# DRIVER.net
KiCad netlist of a schematic drawn in Altium Designer
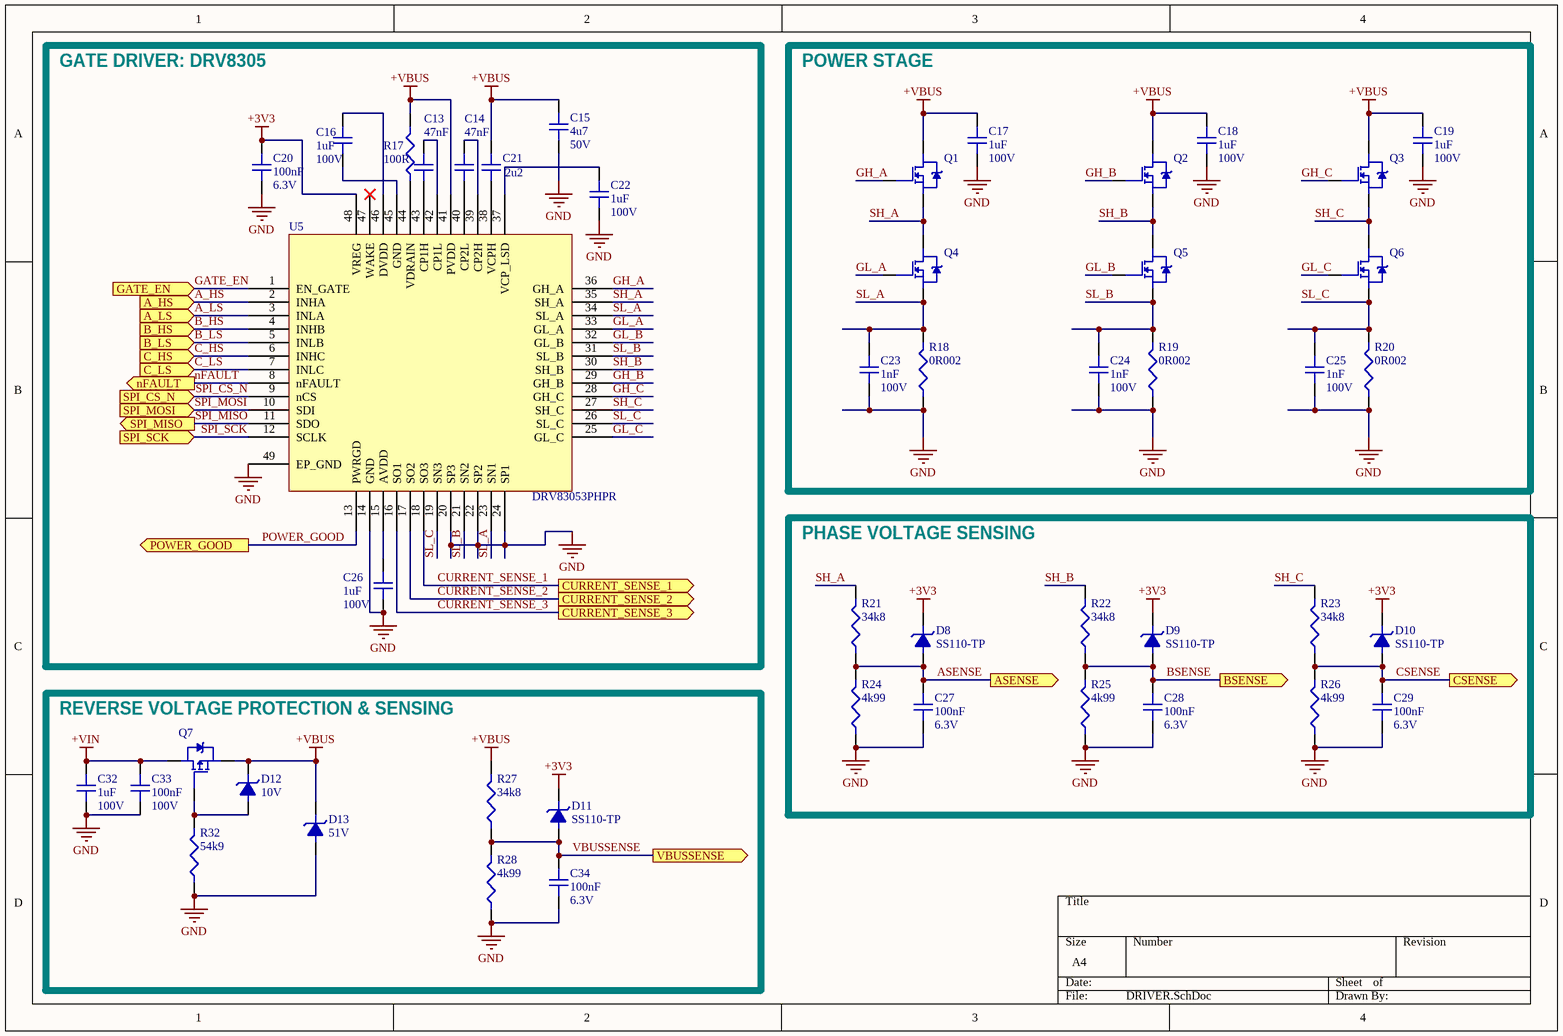
[diagram p0: DRIVER.SchDoc]

(export (version "E")
  (design (tool "Eeschema 10.0.6"))
  (components
    (comp (ref "C13")
      (value "47nF")
      (footprint "C0402")
      (description "CAP CER 0.047uF 50 V,  10%, X7R, CGA Series")
      (fields
        (field (name "MANUFACTURER") "TDK")
        (field (name "MANUFACTURER PART NUMBER") "CGA2B3X7R1H473K050BB")
      )
      (libsource (lib "ESC_SYMBOLS") (part "CGA2B3X7R1H473K050BB"))
    )
    (comp (ref "C14")
      (value "47nF")
      (footprint "C0402")
      (description "CAP CER 0.047uF 50 V,  10%, X7R, CGA Series")
      (fields
        (field (name "MANUFACTURER") "TDK")
        (field (name "MANUFACTURER PART NUMBER") "CGA2B3X7R1H473K050BB")
      )
      (libsource (lib "ESC_SYMBOLS") (part "CGA2B3X7R1H473K050BB"))
    )
    (comp (ref "C15")
      (value "4u7")
      (footprint "C0805")
      (description "CAP CER 4.7uF 50V X5R 10% SMD 0805 85C Embossed T/R")
      (fields
        (field (name "MANUFACTURER") "Samsung")
        (field (name "MANUFACTURER PART NUMBER") "CL21A475KBQNNNE")
        (field (name "VOLTAGE RATING") "50V")
      )
      (libsource (lib "ESC_SYMBOLS") (part "CL21A475KBQNNNE"))
    )
    (comp (ref "C16")
      (value "1uF")
      (footprint "C0805")
      (description "CAP CER 1UF 100V X7S 0805")
      (fields
        (field (name "MANUFACTURER") "TDK")
        (field (name "MANUFACTURER PART NUMBER") "C2012X7S2A105M125AE")
        (field (name "VOLTAGE RATING") "100V")
      )
      (libsource (lib "ESC_SYMBOLS") (part "C2012X7S2A105M125AE"))
    )
    (comp (ref "C17")
      (value "1uF")
      (footprint "C0805")
      (description "CAP CER 1UF 100V X7S 0805")
      (fields
        (field (name "MANUFACTURER") "TDK")
        (field (name "MANUFACTURER PART NUMBER") "C2012X7S2A105M125AE")
        (field (name "VOLTAGE RATING") "100V")
      )
      (libsource (lib "ESC_SYMBOLS") (part "C2012X7S2A105M125AE"))
    )
    (comp (ref "C18")
      (value "1uF")
      (footprint "C0805")
      (description "CAP CER 1UF 100V X7S 0805")
      (fields
        (field (name "MANUFACTURER") "TDK")
        (field (name "MANUFACTURER PART NUMBER") "C2012X7S2A105M125AE")
        (field (name "VOLTAGE RATING") "100V")
      )
      (libsource (lib "ESC_SYMBOLS") (part "C2012X7S2A105M125AE"))
    )
    (comp (ref "C19")
      (value "1uF")
      (footprint "C0805")
      (description "CAP CER 1UF 100V X7S 0805")
      (fields
        (field (name "MANUFACTURER") "TDK")
        (field (name "MANUFACTURER PART NUMBER") "C2012X7S2A105M125AE")
        (field (name "VOLTAGE RATING") "100V")
      )
      (libsource (lib "ESC_SYMBOLS") (part "C2012X7S2A105M125AE"))
    )
    (comp (ref "C20")
      (value "100nF")
      (footprint "C0402")
      (description "CAP CER 0.1uF 6.3V X7R 10% SMD 0402 125C Paper T/R")
      (fields
        (field (name "MANUFACTURER") "Samsung")
        (field (name "MANUFACTURER PART NUMBER") "CL05B104KQ5NNNC")
        (field (name "VOLTAGE RATING") "6.3V")
      )
      (libsource (lib "ESC_SYMBOLS") (part "CL05B104KQ5NNNC"))
    )
    (comp (ref "C21")
      (value "2u2")
      (footprint "C0805")
      (description "CAP CER 2.2UF 50V X5R 0805")
      (fields
        (field (name "MANUFACTURER") "TDK")
        (field (name "MANUFACTURER PART NUMBER") "C2012X5R1H225M125AB")
      )
      (libsource (lib "ESC_SYMBOLS") (part "C2012X5R1H225M125AB"))
    )
    (comp (ref "C22")
      (value "1uF")
      (footprint "C0805")
      (description "CAP CER 1UF 100V X7S 0805")
      (fields
        (field (name "MANUFACTURER") "TDK")
        (field (name "MANUFACTURER PART NUMBER") "C2012X7S2A105M125AE")
        (field (name "VOLTAGE RATING") "100V")
      )
      (libsource (lib "ESC_SYMBOLS") (part "C2012X7S2A105M125AE"))
    )
    (comp (ref "C23")
      (value "1nF")
      (footprint "C0402")
      (description "CAP CER 1000PF 100V X7R 0402")
      (fields
        (field (name "MANUFACTURER") "Murata")
        (field (name "MANUFACTURER PART NUMBER") "GCM155R72A102KA37D")
        (field (name "VOLTAGE") "100V")
      )
      (libsource (lib "ESC_SYMBOLS") (part "GCM155R72A102KA37D"))
    )
    (comp (ref "C24")
      (value "1nF")
      (footprint "C0402")
      (description "CAP CER 1000PF 100V X7R 0402")
      (fields
        (field (name "MANUFACTURER") "Murata")
        (field (name "MANUFACTURER PART NUMBER") "GCM155R72A102KA37D")
        (field (name "VOLTAGE") "100V")
      )
      (libsource (lib "ESC_SYMBOLS") (part "GCM155R72A102KA37D"))
    )
    (comp (ref "C25")
      (value "1nF")
      (footprint "C0402")
      (description "CAP CER 1000PF 100V X7R 0402")
      (fields
        (field (name "MANUFACTURER") "Murata")
        (field (name "MANUFACTURER PART NUMBER") "GCM155R72A102KA37D")
        (field (name "VOLTAGE") "100V")
      )
      (libsource (lib "ESC_SYMBOLS") (part "GCM155R72A102KA37D"))
    )
    (comp (ref "C26")
      (value "1uF")
      (footprint "C0805")
      (description "CAP CER 1UF 100V X7S 0805")
      (fields
        (field (name "MANUFACTURER") "TDK")
        (field (name "MANUFACTURER PART NUMBER") "C2012X7S2A105M125AE")
        (field (name "VOLTAGE RATING") "100V")
      )
      (libsource (lib "ESC_SYMBOLS") (part "C2012X7S2A105M125AE"))
    )
    (comp (ref "C27")
      (value "100nF")
      (footprint "C0402")
      (description "CAP CER 0.1uF 6.3V X7R 10% SMD 0402 125C Paper T/R")
      (fields
        (field (name "MANUFACTURER") "Samsung")
        (field (name "MANUFACTURER PART NUMBER") "CL05B104KQ5NNNC")
        (field (name "VOLTAGE RATING") "6.3V")
      )
      (libsource (lib "ESC_SYMBOLS") (part "CL05B104KQ5NNNC"))
    )
    (comp (ref "C28")
      (value "100nF")
      (footprint "C0402")
      (description "CAP CER 0.1uF 6.3V X7R 10% SMD 0402 125C Paper T/R")
      (fields
        (field (name "MANUFACTURER") "Samsung")
        (field (name "MANUFACTURER PART NUMBER") "CL05B104KQ5NNNC")
        (field (name "VOLTAGE RATING") "6.3V")
      )
      (libsource (lib "ESC_SYMBOLS") (part "CL05B104KQ5NNNC"))
    )
    (comp (ref "C29")
      (value "100nF")
      (footprint "C0402")
      (description "CAP CER 0.1uF 6.3V X7R 10% SMD 0402 125C Paper T/R")
      (fields
        (field (name "MANUFACTURER") "Samsung")
        (field (name "MANUFACTURER PART NUMBER") "CL05B104KQ5NNNC")
        (field (name "VOLTAGE RATING") "6.3V")
      )
      (libsource (lib "ESC_SYMBOLS") (part "CL05B104KQ5NNNC"))
    )
    (comp (ref "C32")
      (value "1uF")
      (footprint "C0805")
      (description "CAP CER 1UF 100V X7S 0805")
      (fields
        (field (name "MANUFACTURER") "TDK")
        (field (name "MANUFACTURER PART NUMBER") "C2012X7S2A105M125AE")
        (field (name "VOLTAGE RATING") "100V")
      )
      (libsource (lib "ESC_SYMBOLS") (part "C2012X7S2A105M125AE"))
    )
    (comp (ref "C33")
      (value "100nF")
      (footprint "C0805")
      (fields
        (field (name "MANUFACTURER") "Samsung")
        (field (name "MANUFACTURER PART NUMBER") "CL21B104KCFWPNE")
        (field (name "TOLERANCE") "10%")
        (field (name "VOLTAGE RATING") "100V")
      )
      (libsource (lib "ESC_SYMBOLS") (part "CL21B104KCFWPNE"))
    )
    (comp (ref "C34")
      (value "100nF")
      (footprint "C0805")
      (description "CAP CER 0.10uF 6.3V X7R MLCC - SMD/SMT 6.3volts 0.1uF X7R 10%")
      (fields
        (field (name "MANUFACTURER") "KEMET")
        (field (name "MANUFACTURER PART NUMBER") "C0805C104K9RACTU")
        (field (name "VOLTAGE RATING") "6.3V")
      )
      (libsource (lib "ESC_SYMBOLS") (part "C0805C104K9RACTU"))
    )
    (comp (ref "D8")
      (value "SS110-TP")
      (footprint "DO-214AA_Diode")
      (description "DIODE SCHOTTKY 100V 1A SMA")
      (fields (field (name "MANUFACTURER") "MCC"))
      (libsource (lib "ESC_SYMBOLS") (part "SS110-TP"))
    )
    (comp (ref "D9")
      (value "SS110-TP")
      (footprint "DO-214AA_Diode")
      (description "DIODE SCHOTTKY 100V 1A SMA")
      (fields (field (name "MANUFACTURER") "MCC"))
      (libsource (lib "ESC_SYMBOLS") (part "SS110-TP"))
    )
    (comp (ref "D10")
      (value "SS110-TP")
      (footprint "DO-214AA_Diode")
      (description "DIODE SCHOTTKY 100V 1A SMA")
      (fields (field (name "MANUFACTURER") "MCC"))
      (libsource (lib "ESC_SYMBOLS") (part "SS110-TP"))
    )
    (comp (ref "D11")
      (value "SS110-TP")
      (footprint "DO-214AA_Diode")
      (description "DIODE SCHOTTKY 100V 1A SMA")
      (fields (field (name "MANUFACTURER") "MCC"))
      (libsource (lib "ESC_SYMBOLS") (part "SS110-TP"))
    )
    (comp (ref "D12")
      (value "10V")
      (footprint "DO-214AC")
      (description "DIODE ZENER 10V 5% 1W 2-Pin SMA T/R")
      (fields (field (name "MANUFACTURER") "Diodes") (field (name "MANUFACTURER PART NUMBER") "SMAZ10-13-F"))
      (libsource (lib "ESC_SYMBOLS") (part "SMAZ10-13-F"))
    )
    (comp (ref "D13")
      (value "51V")
      (footprint "DO-214AB")
      (description "DIODE ZENER 51V 5W")
      (fields
        (field (name "MANUFACTURER") "Taiwan Semiconductor")
        (field (name "MANUFACTURER PART NUMBER") "1PGSMC5369HR7G")
      )
      (libsource (lib "ESC_SYMBOLS") (part "1PGSMC5369HR7G"))
    )
    (comp (ref "Q1")
      (value "SIR186DP-T1-RE3")
      (footprint "SO-8 PowerPAK")
      (description "MOSFET N-CH 60V 60A 4.5mOhm Rds(ON)")
      (fields (field (name "MANUFACTURER") "Vishay Siliconix"))
      (libsource (lib "ESC_SYMBOLS") (part "SIR186DP-T1-RE3"))
    )
    (comp (ref "Q2")
      (value "SIR186DP-T1-RE3")
      (footprint "SO-8 PowerPAK")
      (description "MOSFET N-CH 60V 60A 4.5mOhm Rds(ON)")
      (fields (field (name "MANUFACTURER") "Vishay Siliconix"))
      (libsource (lib "ESC_SYMBOLS") (part "SIR186DP-T1-RE3"))
    )
    (comp (ref "Q3")
      (value "SIR186DP-T1-RE3")
      (footprint "SO-8 PowerPAK")
      (description "MOSFET N-CH 60V 60A 4.5mOhm Rds(ON)")
      (fields (field (name "MANUFACTURER") "Vishay Siliconix"))
      (libsource (lib "ESC_SYMBOLS") (part "SIR186DP-T1-RE3"))
    )
    (comp (ref "Q4")
      (value "SIR186DP-T1-RE3")
      (footprint "SO-8 PowerPAK")
      (description "MOSFET N-CH 60V 60A 4.5mOhm Rds(ON)")
      (fields (field (name "MANUFACTURER") "Vishay Siliconix"))
      (libsource (lib "ESC_SYMBOLS") (part "SIR186DP-T1-RE3"))
    )
    (comp (ref "Q5")
      (value "SIR186DP-T1-RE3")
      (footprint "SO-8 PowerPAK")
      (description "MOSFET N-CH 60V 60A 4.5mOhm Rds(ON)")
      (fields (field (name "MANUFACTURER") "Vishay Siliconix"))
      (libsource (lib "ESC_SYMBOLS") (part "SIR186DP-T1-RE3"))
    )
    (comp (ref "Q6")
      (value "SIR186DP-T1-RE3")
      (footprint "SO-8 PowerPAK")
      (description "MOSFET N-CH 60V 60A 4.5mOhm Rds(ON)")
      (fields (field (name "MANUFACTURER") "Vishay Siliconix"))
      (libsource (lib "ESC_SYMBOLS") (part "SIR186DP-T1-RE3"))
    )
    (comp (ref "Q7")
      (value "FDWS9509L-F085")
      (footprint "SO-8 PowerPAK")
      (description "MOSFET P-CH PWR56 40V 8 MOHM")
      (fields (field (name "MANUFACTURER") "ON Semiconductor"))
      (libsource (lib "ESC_SYMBOLS") (part "FDWS9509L-F085"))
    )
    (comp (ref "R17")
      (value "100R")
      (footprint "R0402")
      (description "RES SMD 100 OHM 5% 1/16W 0402")
      (fields
        (field (name "MANUFACTURER") "Yageo")
        (field (name "MANUFACTURER PART NUMBER") "RC0402JR-07100RL")
      )
      (libsource (lib "ESC_SYMBOLS") (part "RC0402JR-07100RL"))
    )
    (comp (ref "R18")
      (value "0R002")
      (footprint "R2512")
      (description "RES SMD 0.002 OHM 1% 5W 2512")
      (fields
        (field (name "MANUFACTURER") "Vishay Dale")
        (field (name "MANUFACTURER PART NUMBER") "WSLF25122L000FEA")
      )
      (libsource (lib "ESC_SYMBOLS") (part "WSLF25122L000FEA"))
    )
    (comp (ref "R19")
      (value "0R002")
      (footprint "R2512")
      (description "RES SMD 0.002 OHM 1% 5W 2512")
      (fields
        (field (name "MANUFACTURER") "Vishay Dale")
        (field (name "MANUFACTURER PART NUMBER") "WSLF25122L000FEA")
      )
      (libsource (lib "ESC_SYMBOLS") (part "WSLF25122L000FEA"))
    )
    (comp (ref "R20")
      (value "0R002")
      (footprint "R2512")
      (description "RES SMD 0.002 OHM 1% 5W 2512")
      (fields
        (field (name "MANUFACTURER") "Vishay Dale")
        (field (name "MANUFACTURER PART NUMBER") "WSLF25122L000FEA")
      )
      (libsource (lib "ESC_SYMBOLS") (part "WSLF25122L000FEA"))
    )
    (comp (ref "R21")
      (value "34k8")
      (footprint "R0402")
      (description "RES SMD 34.8K OHM 1% 1/16W 0402")
      (fields
        (field (name "MANUFACTURER") "Yageo")
        (field (name "MANUFACTURER PART NUMBER") "RC0402FR-0734K8L")
      )
      (libsource (lib "ESC_SYMBOLS") (part "RC0402FR-0734K8L"))
    )
    (comp (ref "R22")
      (value "34k8")
      (footprint "R0402")
      (description "RES SMD 34.8K OHM 1% 1/16W 0402")
      (fields
        (field (name "MANUFACTURER") "Yageo")
        (field (name "MANUFACTURER PART NUMBER") "RC0402FR-0734K8L")
      )
      (libsource (lib "ESC_SYMBOLS") (part "RC0402FR-0734K8L"))
    )
    (comp (ref "R23")
      (value "34k8")
      (footprint "R0402")
      (description "RES SMD 34.8K OHM 1% 1/16W 0402")
      (fields
        (field (name "MANUFACTURER") "Yageo")
        (field (name "MANUFACTURER PART NUMBER") "RC0402FR-0734K8L")
      )
      (libsource (lib "ESC_SYMBOLS") (part "RC0402FR-0734K8L"))
    )
    (comp (ref "R24")
      (value "4k99")
      (footprint "R0402")
      (description "RES SMD 4.99K OHM 1/16W 0402")
      (fields
        (field (name "MANUFACTURER") "Vishay")
        (field (name "MANUFACTURER PART NUMBER") "CRCW04024R99FKEDC")
      )
      (libsource (lib "ESC_SYMBOLS") (part "CRCW04024R99FKEDC"))
    )
    (comp (ref "R25")
      (value "4k99")
      (footprint "R0402")
      (description "RES SMD 4.99K OHM 1/16W 0402")
      (fields
        (field (name "MANUFACTURER") "Vishay")
        (field (name "MANUFACTURER PART NUMBER") "CRCW04024R99FKEDC")
      )
      (libsource (lib "ESC_SYMBOLS") (part "CRCW04024R99FKEDC"))
    )
    (comp (ref "R26")
      (value "4k99")
      (footprint "R0402")
      (description "RES SMD 4.99K OHM 1/16W 0402")
      (fields
        (field (name "MANUFACTURER") "Vishay")
        (field (name "MANUFACTURER PART NUMBER") "CRCW04024R99FKEDC")
      )
      (libsource (lib "ESC_SYMBOLS") (part "CRCW04024R99FKEDC"))
    )
    (comp (ref "R27")
      (value "34k8")
      (footprint "R0402")
      (description "RES SMD 34.8K OHM 1% 1/16W 0402")
      (fields
        (field (name "MANUFACTURER") "Yageo")
        (field (name "MANUFACTURER PART NUMBER") "RC0402FR-0734K8L")
      )
      (libsource (lib "ESC_SYMBOLS") (part "RC0402FR-0734K8L"))
    )
    (comp (ref "R28")
      (value "4k99")
      (footprint "R0402")
      (description "RES SMD 4.99K OHM 1/16W 0402")
      (fields
        (field (name "MANUFACTURER") "Vishay")
        (field (name "MANUFACTURER PART NUMBER") "CRCW04024R99FKEDC")
      )
      (libsource (lib "ESC_SYMBOLS") (part "CRCW04024R99FKEDC"))
    )
    (comp (ref "R32")
      (value "54k9")
      (footprint "R0402")
      (description "RES SMD 54.9K OHM 1/10W 0402 54.9 Ohm 1% 0.1W(1/10W) ±100ppm/C Molded SMD Automotive Punched T/R")
      (fields
        (field (name "MANUFACTURER") "Panasonic")
        (field (name "MANUFACTURER PART NUMBER") "ERJ-2RKF54R9X")
      )
      (libsource (lib "ESC_SYMBOLS") (part "ERJ-2RKF54R9X"))
    )
    (comp (ref "U5")
      (value "DRV83053PHPR")
      (footprint "PQFP_EP-48")
      (description "IC 3-Phase Gate Driver IC 4.4V to 45V 48-Pin HTQFP T/R")
      (fields (field (name "MANUFACTURER") "Texas Instruments"))
      (libsource (lib "ESC_SYMBOLS") (part "DRV83053PHPR"))
    )
  )
  (nets
    (net (code "1") (name "+3V3") (class "Default")
      (node (ref "C20") (pin "2") (pinfunction "2_2") (pintype "passive"))
      (node (ref "D10") (pin "2") (pinfunction "2_2") (pintype "passive"))
      (node (ref "D11") (pin "2") (pinfunction "2_2") (pintype "passive"))
      (node (ref "D8") (pin "2") (pinfunction "2_2") (pintype "passive"))
      (node (ref "D9") (pin "2") (pinfunction "2_2") (pintype "passive"))
      (node (ref "U5") (pin "48") (pinfunction "VREG_48") (pintype "passive"))
    )
    (net (code "2") (name "+VBUS") (class "Default")
      (node (ref "C15") (pin "2") (pinfunction "2_2") (pintype "passive"))
      (node (ref "C17") (pin "2") (pinfunction "2_2") (pintype "passive"))
      (node (ref "C18") (pin "2") (pinfunction "2_2") (pintype "passive"))
      (node (ref "C19") (pin "2") (pinfunction "2_2") (pintype "passive"))
      (node (ref "C21") (pin "2") (pinfunction "2_2") (pintype "passive"))
      (node (ref "D12") (pin "1") (pinfunction "1_1") (pintype "passive"))
      (node (ref "D13") (pin "1") (pinfunction "1_1") (pintype "passive"))
      (node (ref "Q1") (pin "2") (pinfunction "2_2") (pintype "passive"))
      (node (ref "Q2") (pin "2") (pinfunction "2_2") (pintype "passive"))
      (node (ref "Q3") (pin "2") (pinfunction "2_2") (pintype "passive"))
      (node (ref "Q7") (pin "3") (pinfunction "3_3") (pintype "passive"))
      (node (ref "R17") (pin "2") (pinfunction "2_2") (pintype "passive"))
      (node (ref "R27") (pin "2") (pinfunction "2_2") (pintype "passive"))
      (node (ref "U5") (pin "41") (pinfunction "PVDD_41") (pintype "passive"))
    )
    (net (code "3") (name "+VIN") (class "Default")
      (node (ref "C32") (pin "2") (pinfunction "2_2") (pintype "passive"))
      (node (ref "C33") (pin "2") (pinfunction "2_2") (pintype "passive"))
      (node (ref "Q7") (pin "2") (pinfunction "2_2") (pintype "passive"))
    )
    (net (code "4") (name "/ASENSE") (class "Default")
      (node (ref "C27") (pin "2") (pinfunction "2_2") (pintype "passive"))
      (node (ref "D8") (pin "1") (pinfunction "1_1") (pintype "passive"))
      (node (ref "R21") (pin "1") (pinfunction "1_1") (pintype "passive"))
      (node (ref "R24") (pin "2") (pinfunction "2_2") (pintype "passive"))
    )
    (net (code "5") (name "/A_HS") (class "Default")
      (node (ref "U5") (pin "2") (pinfunction "INHA_2") (pintype "passive"))
    )
    (net (code "6") (name "/A_LS") (class "Default")
      (node (ref "U5") (pin "3") (pinfunction "INLA_3") (pintype "passive"))
    )
    (net (code "7") (name "/BSENSE") (class "Default")
      (node (ref "C28") (pin "2") (pinfunction "2_2") (pintype "passive"))
      (node (ref "D9") (pin "1") (pinfunction "1_1") (pintype "passive"))
      (node (ref "R22") (pin "1") (pinfunction "1_1") (pintype "passive"))
      (node (ref "R25") (pin "2") (pinfunction "2_2") (pintype "passive"))
    )
    (net (code "8") (name "/B_HS") (class "Default")
      (node (ref "U5") (pin "4") (pinfunction "INHB_4") (pintype "passive"))
    )
    (net (code "9") (name "/B_LS") (class "Default")
      (node (ref "U5") (pin "5") (pinfunction "INLB_5") (pintype "passive"))
    )
    (net (code "10") (name "/CSENSE") (class "Default")
      (node (ref "C29") (pin "2") (pinfunction "2_2") (pintype "passive"))
      (node (ref "D10") (pin "1") (pinfunction "1_1") (pintype "passive"))
      (node (ref "R23") (pin "1") (pinfunction "1_1") (pintype "passive"))
      (node (ref "R26") (pin "2") (pinfunction "2_2") (pintype "passive"))
    )
    (net (code "11") (name "/CURRENT_SENSE_1") (class "Default")
      (node (ref "U5") (pin "18") (pinfunction "SO3_18") (pintype "passive"))
    )
    (net (code "12") (name "/CURRENT_SENSE_2") (class "Default")
      (node (ref "U5") (pin "17") (pinfunction "SO2_17") (pintype "passive"))
    )
    (net (code "13") (name "/CURRENT_SENSE_3") (class "Default")
      (node (ref "U5") (pin "16") (pinfunction "SO1_16") (pintype "passive"))
    )
    (net (code "14") (name "/C_HS") (class "Default")
      (node (ref "U5") (pin "6") (pinfunction "INHC_6") (pintype "passive"))
    )
    (net (code "15") (name "/C_LS") (class "Default")
      (node (ref "U5") (pin "7") (pinfunction "INLC_7") (pintype "passive"))
    )
    (net (code "16") (name "/GATE_EN") (class "Default")
      (node (ref "U5") (pin "1") (pinfunction "EN_GATE_1") (pintype "passive"))
    )
    (net (code "17") (name "/GH_A") (class "Default")
      (node (ref "Q1") (pin "1") (pinfunction "1_1") (pintype "passive"))
      (node (ref "U5") (pin "36") (pinfunction "GH_A_36") (pintype "passive"))
    )
    (net (code "18") (name "/GH_B") (class "Default")
      (node (ref "Q2") (pin "1") (pinfunction "1_1") (pintype "passive"))
      (node (ref "U5") (pin "29") (pinfunction "GH_B_29") (pintype "passive"))
    )
    (net (code "19") (name "/GH_C") (class "Default")
      (node (ref "Q3") (pin "1") (pinfunction "1_1") (pintype "passive"))
      (node (ref "U5") (pin "28") (pinfunction "GH_C_28") (pintype "passive"))
    )
    (net (code "20") (name "/GL_A") (class "Default")
      (node (ref "Q4") (pin "1") (pinfunction "1_1") (pintype "passive"))
      (node (ref "U5") (pin "33") (pinfunction "GL_A_33") (pintype "passive"))
    )
    (net (code "21") (name "/GL_B") (class "Default")
      (node (ref "Q5") (pin "1") (pinfunction "1_1") (pintype "passive"))
      (node (ref "U5") (pin "32") (pinfunction "GL_B_32") (pintype "passive"))
    )
    (net (code "22") (name "/GL_C") (class "Default")
      (node (ref "Q6") (pin "1") (pinfunction "1_1") (pintype "passive"))
      (node (ref "U5") (pin "25") (pinfunction "GL_C_25") (pintype "passive"))
    )
    (net (code "23") (name "/POWER_GOOD") (class "Default")
      (node (ref "U5") (pin "13") (pinfunction "PWRGD_13") (pintype "passive"))
    )
    (net (code "24") (name "/SH_A") (class "Default")
      (node (ref "Q1") (pin "3") (pinfunction "3_3") (pintype "passive"))
      (node (ref "Q4") (pin "2") (pinfunction "2_2") (pintype "passive"))
      (node (ref "R21") (pin "2") (pinfunction "2_2") (pintype "passive"))
      (node (ref "U5") (pin "35") (pinfunction "SH_A_35") (pintype "passive"))
    )
    (net (code "25") (name "/SH_B") (class "Default")
      (node (ref "Q2") (pin "3") (pinfunction "3_3") (pintype "passive"))
      (node (ref "Q5") (pin "2") (pinfunction "2_2") (pintype "passive"))
      (node (ref "R22") (pin "2") (pinfunction "2_2") (pintype "passive"))
      (node (ref "U5") (pin "30") (pinfunction "SH_B_30") (pintype "passive"))
    )
    (net (code "26") (name "/SH_C") (class "Default")
      (node (ref "Q3") (pin "3") (pinfunction "3_3") (pintype "passive"))
      (node (ref "Q6") (pin "2") (pinfunction "2_2") (pintype "passive"))
      (node (ref "R23") (pin "2") (pinfunction "2_2") (pintype "passive"))
      (node (ref "U5") (pin "27") (pinfunction "SH_C_27") (pintype "passive"))
    )
    (net (code "27") (name "/SL_A") (class "Default")
      (node (ref "C23") (pin "2") (pinfunction "2_2") (pintype "passive"))
      (node (ref "Q4") (pin "3") (pinfunction "3_3") (pintype "passive"))
      (node (ref "R18") (pin "2") (pinfunction "2_2") (pintype "passive"))
      (node (ref "U5") (pin "23") (pinfunction "SN1_23") (pintype "passive"))
      (node (ref "U5") (pin "34") (pinfunction "SL_A_34") (pintype "passive"))
    )
    (net (code "28") (name "/SL_B") (class "Default")
      (node (ref "C24") (pin "2") (pinfunction "2_2") (pintype "passive"))
      (node (ref "Q5") (pin "3") (pinfunction "3_3") (pintype "passive"))
      (node (ref "R19") (pin "2") (pinfunction "2_2") (pintype "passive"))
      (node (ref "U5") (pin "21") (pinfunction "SN2_21") (pintype "passive"))
      (node (ref "U5") (pin "31") (pinfunction "SL_B_31") (pintype "passive"))
    )
    (net (code "29") (name "/SL_C") (class "Default")
      (node (ref "C25") (pin "2") (pinfunction "2_2") (pintype "passive"))
      (node (ref "Q6") (pin "3") (pinfunction "3_3") (pintype "passive"))
      (node (ref "R20") (pin "2") (pinfunction "2_2") (pintype "passive"))
      (node (ref "U5") (pin "19") (pinfunction "SN3_19") (pintype "passive"))
      (node (ref "U5") (pin "26") (pinfunction "SL_C_26") (pintype "passive"))
    )
    (net (code "30") (name "/SPI_CS_N") (class "Default")
      (node (ref "U5") (pin "9") (pinfunction "nCS_9") (pintype "passive"))
    )
    (net (code "31") (name "/SPI_MISO") (class "Default")
      (node (ref "U5") (pin "11") (pinfunction "SDO_11") (pintype "passive"))
    )
    (net (code "32") (name "/SPI_MOSI") (class "Default")
      (node (ref "U5") (pin "10") (pinfunction "SDI_10") (pintype "passive"))
    )
    (net (code "33") (name "/SPI_SCK") (class "Default")
      (node (ref "U5") (pin "12") (pinfunction "SCLK_12") (pintype "passive"))
    )
    (net (code "34") (name "/VBUSSENSE") (class "Default")
      (node (ref "C34") (pin "2") (pinfunction "2_2") (pintype "passive"))
      (node (ref "D11") (pin "1") (pinfunction "1_1") (pintype "passive"))
      (node (ref "R27") (pin "1") (pinfunction "1_1") (pintype "passive"))
      (node (ref "R28") (pin "2") (pinfunction "2_2") (pintype "passive"))
    )
    (net (code "35") (name "/nFAULT") (class "Default")
      (node (ref "U5") (pin "8") (pinfunction "nFAULT_8") (pintype "passive"))
    )
    (net (code "36") (name "GND") (class "Default")
      (node (ref "C15") (pin "1") (pinfunction "1_1") (pintype "passive"))
      (node (ref "C17") (pin "1") (pinfunction "1_1") (pintype "passive"))
      (node (ref "C18") (pin "1") (pinfunction "1_1") (pintype "passive"))
      (node (ref "C19") (pin "1") (pinfunction "1_1") (pintype "passive"))
      (node (ref "C20") (pin "1") (pinfunction "1_1") (pintype "passive"))
      (node (ref "C22") (pin "1") (pinfunction "1_1") (pintype "passive"))
      (node (ref "C23") (pin "1") (pinfunction "1_1") (pintype "passive"))
      (node (ref "C24") (pin "1") (pinfunction "1_1") (pintype "passive"))
      (node (ref "C25") (pin "1") (pinfunction "1_1") (pintype "passive"))
      (node (ref "C26") (pin "1") (pinfunction "1_1") (pintype "passive"))
      (node (ref "C27") (pin "1") (pinfunction "1_1") (pintype "passive"))
      (node (ref "C28") (pin "1") (pinfunction "1_1") (pintype "passive"))
      (node (ref "C29") (pin "1") (pinfunction "1_1") (pintype "passive"))
      (node (ref "C32") (pin "1") (pinfunction "1_1") (pintype "passive"))
      (node (ref "C33") (pin "1") (pinfunction "1_1") (pintype "passive"))
      (node (ref "C34") (pin "1") (pinfunction "1_1") (pintype "passive"))
      (node (ref "D13") (pin "2") (pinfunction "2_2") (pintype "passive"))
      (node (ref "R18") (pin "1") (pinfunction "1_1") (pintype "passive"))
      (node (ref "R19") (pin "1") (pinfunction "1_1") (pintype "passive"))
      (node (ref "R20") (pin "1") (pinfunction "1_1") (pintype "passive"))
      (node (ref "R24") (pin "1") (pinfunction "1_1") (pintype "passive"))
      (node (ref "R25") (pin "1") (pinfunction "1_1") (pintype "passive"))
      (node (ref "R26") (pin "1") (pinfunction "1_1") (pintype "passive"))
      (node (ref "R28") (pin "1") (pinfunction "1_1") (pintype "passive"))
      (node (ref "R32") (pin "1") (pinfunction "1_1") (pintype "passive"))
      (node (ref "U5") (pin "14") (pinfunction "GND_14") (pintype "passive"))
      (node (ref "U5") (pin "20") (pinfunction "SP3_20") (pintype "passive"))
      (node (ref "U5") (pin "22") (pinfunction "SP2_22") (pintype "passive"))
      (node (ref "U5") (pin "24") (pinfunction "SP1_24") (pintype "passive"))
      (node (ref "U5") (pin "49") (pinfunction "EP_GND_49") (pintype "passive"))
    )
    (net (code "37") (name "Net-(C16-Pad1)") (class "Default")
      (node (ref "C16") (pin "1") (pinfunction "1_1") (pintype "passive"))
      (node (ref "U5") (pin "45") (pinfunction "GND_45") (pintype "passive"))
    )
    (net (code "38") (name "Net-(D12-Pad2)") (class "Default")
      (node (ref "D12") (pin "2") (pinfunction "2_2") (pintype "passive"))
      (node (ref "Q7") (pin "1") (pinfunction "1_1") (pintype "passive"))
      (node (ref "R32") (pin "2") (pinfunction "2_2") (pintype "passive"))
    )
    (net (code "39") (name "Net-(U5-AVDD)") (class "Default")
      (node (ref "C26") (pin "2") (pinfunction "2_2") (pintype "passive"))
      (node (ref "U5") (pin "15") (pinfunction "AVDD_15") (pintype "passive"))
    )
    (net (code "40") (name "Net-(U5-CP1H)") (class "Default")
      (node (ref "C13") (pin "1") (pinfunction "1_1") (pintype "passive"))
      (node (ref "U5") (pin "43") (pinfunction "CP1H_43") (pintype "passive"))
    )
    (net (code "41") (name "Net-(U5-CP1L)") (class "Default")
      (node (ref "C13") (pin "2") (pinfunction "2_2") (pintype "passive"))
      (node (ref "U5") (pin "42") (pinfunction "CP1L_42") (pintype "passive"))
    )
    (net (code "42") (name "Net-(U5-CP2H)") (class "Default")
      (node (ref "C14") (pin "2") (pinfunction "2_2") (pintype "passive"))
      (node (ref "U5") (pin "39") (pinfunction "CP2H_39") (pintype "passive"))
    )
    (net (code "43") (name "Net-(U5-CP2L)") (class "Default")
      (node (ref "C14") (pin "1") (pinfunction "1_1") (pintype "passive"))
      (node (ref "U5") (pin "40") (pinfunction "CP2L_40") (pintype "passive"))
    )
    (net (code "44") (name "Net-(U5-DVDD)") (class "Default")
      (node (ref "C16") (pin "2") (pinfunction "2_2") (pintype "passive"))
      (node (ref "U5") (pin "46") (pinfunction "DVDD_46") (pintype "passive"))
    )
    (net (code "45") (name "Net-(U5-VCPH)") (class "Default")
      (node (ref "C21") (pin "1") (pinfunction "1_1") (pintype "passive"))
      (node (ref "U5") (pin "38") (pinfunction "VCPH_38") (pintype "passive"))
    )
    (net (code "46") (name "Net-(U5-VCP_LSD)") (class "Default")
      (node (ref "C22") (pin "2") (pinfunction "2_2") (pintype "passive"))
      (node (ref "U5") (pin "37") (pinfunction "VCP_LSD_37") (pintype "passive"))
    )
    (net (code "47") (name "Net-(U5-VDRAIN)") (class "Default")
      (node (ref "R17") (pin "1") (pinfunction "1_1") (pintype "passive"))
      (node (ref "U5") (pin "44") (pinfunction "VDRAIN_44") (pintype "passive"))
    )
    (net (code "48") (name "unconnected-(U5-WAKE-Pad47)") (class "Default")
      (node (ref "U5") (pin "47") (pinfunction "WAKE_47") (pintype "passive+no_connect"))
    )
  )
)
